# power_electronicsV2_1.net
KiCad netlist of a schematic drawn in EAGLE
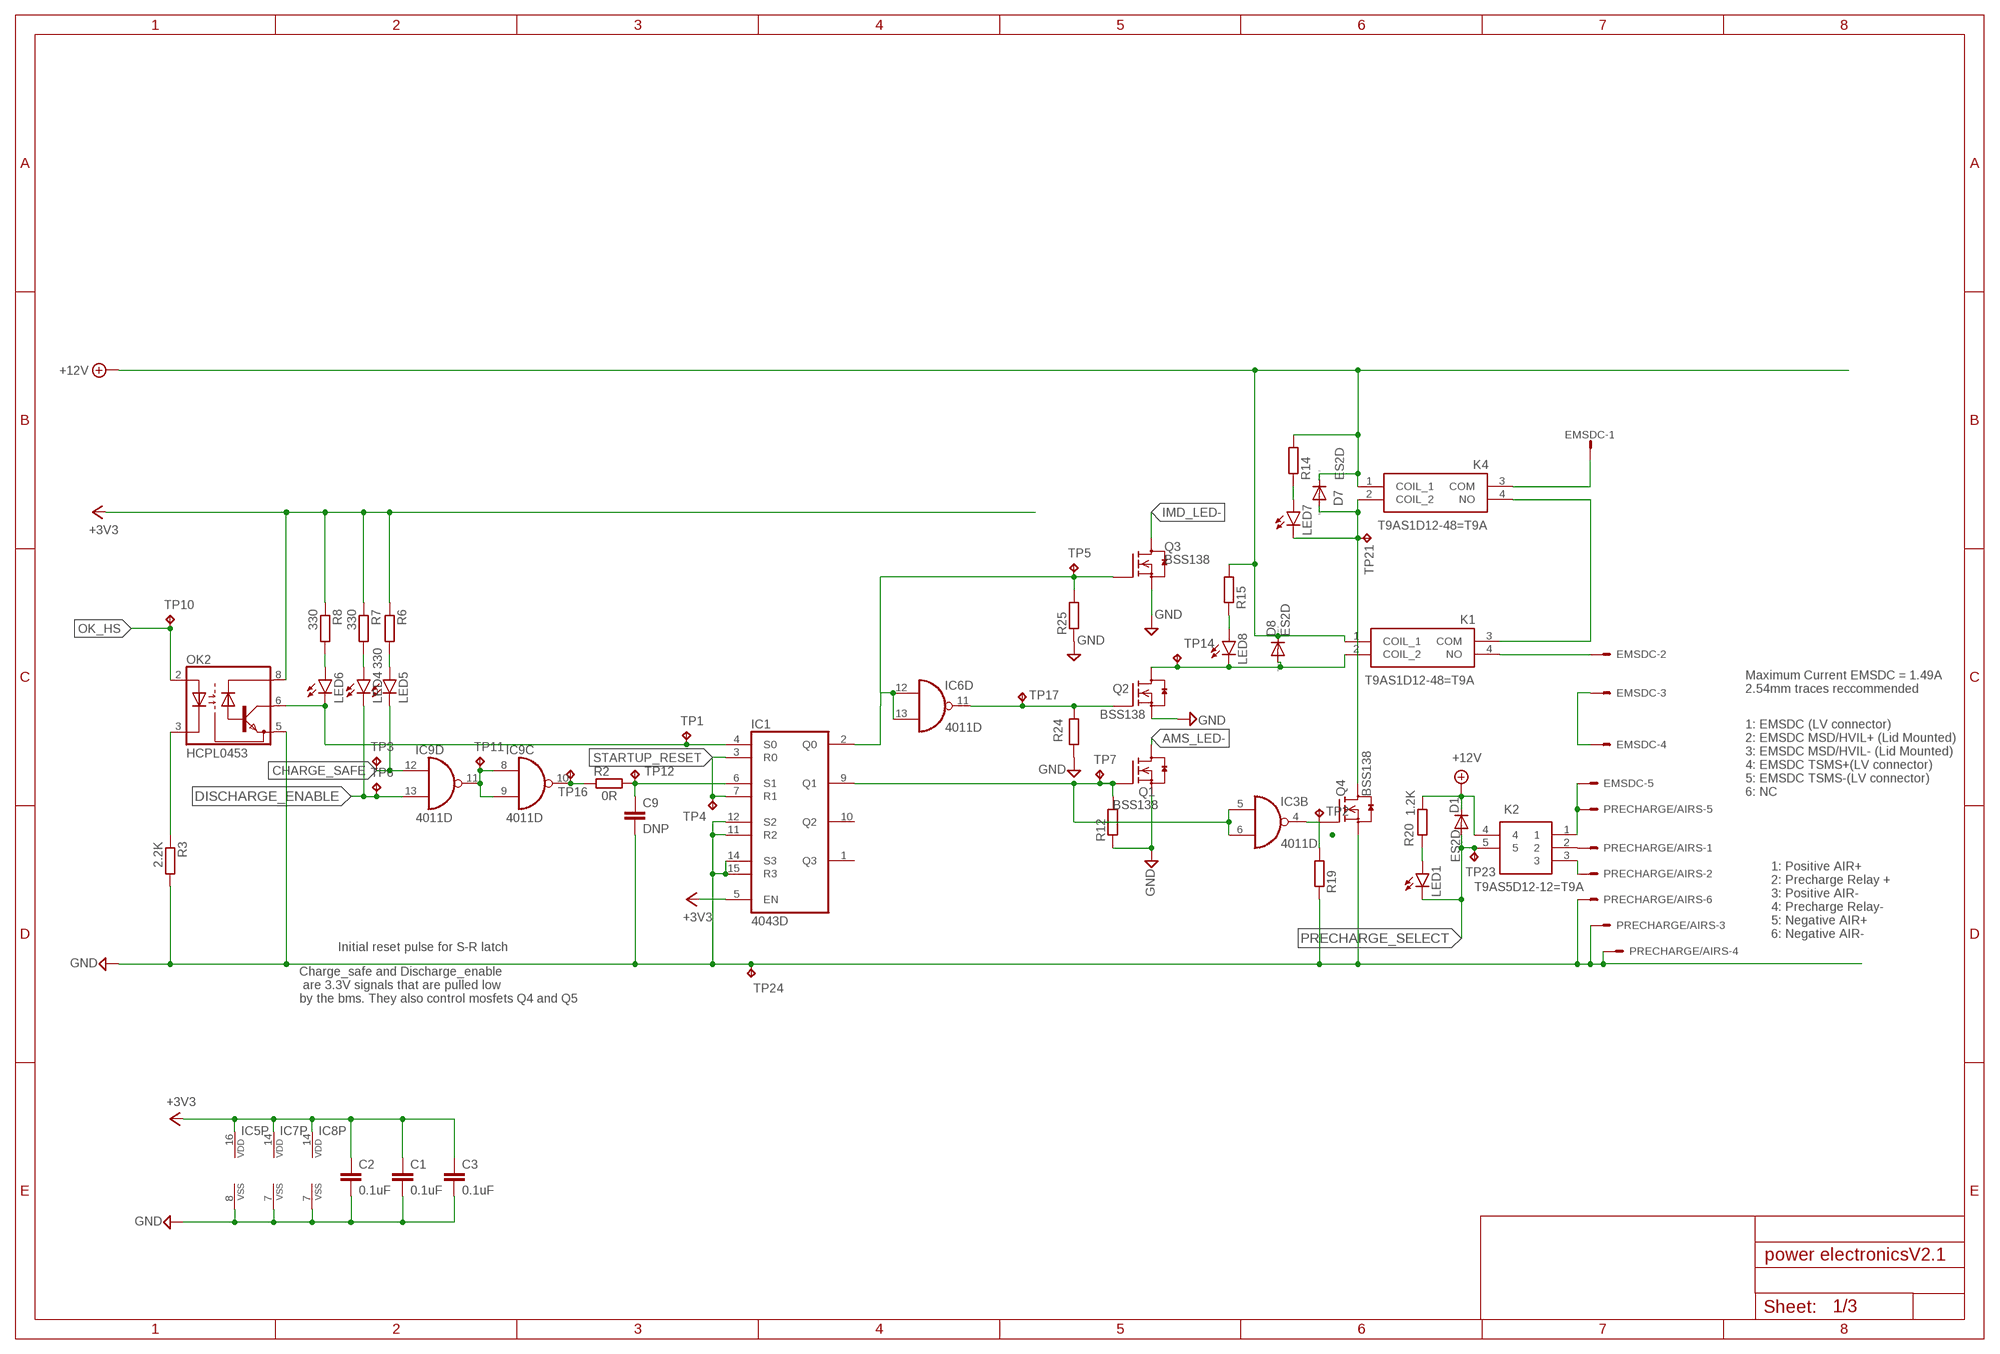
[diagram p0: schematic, sheet 1]
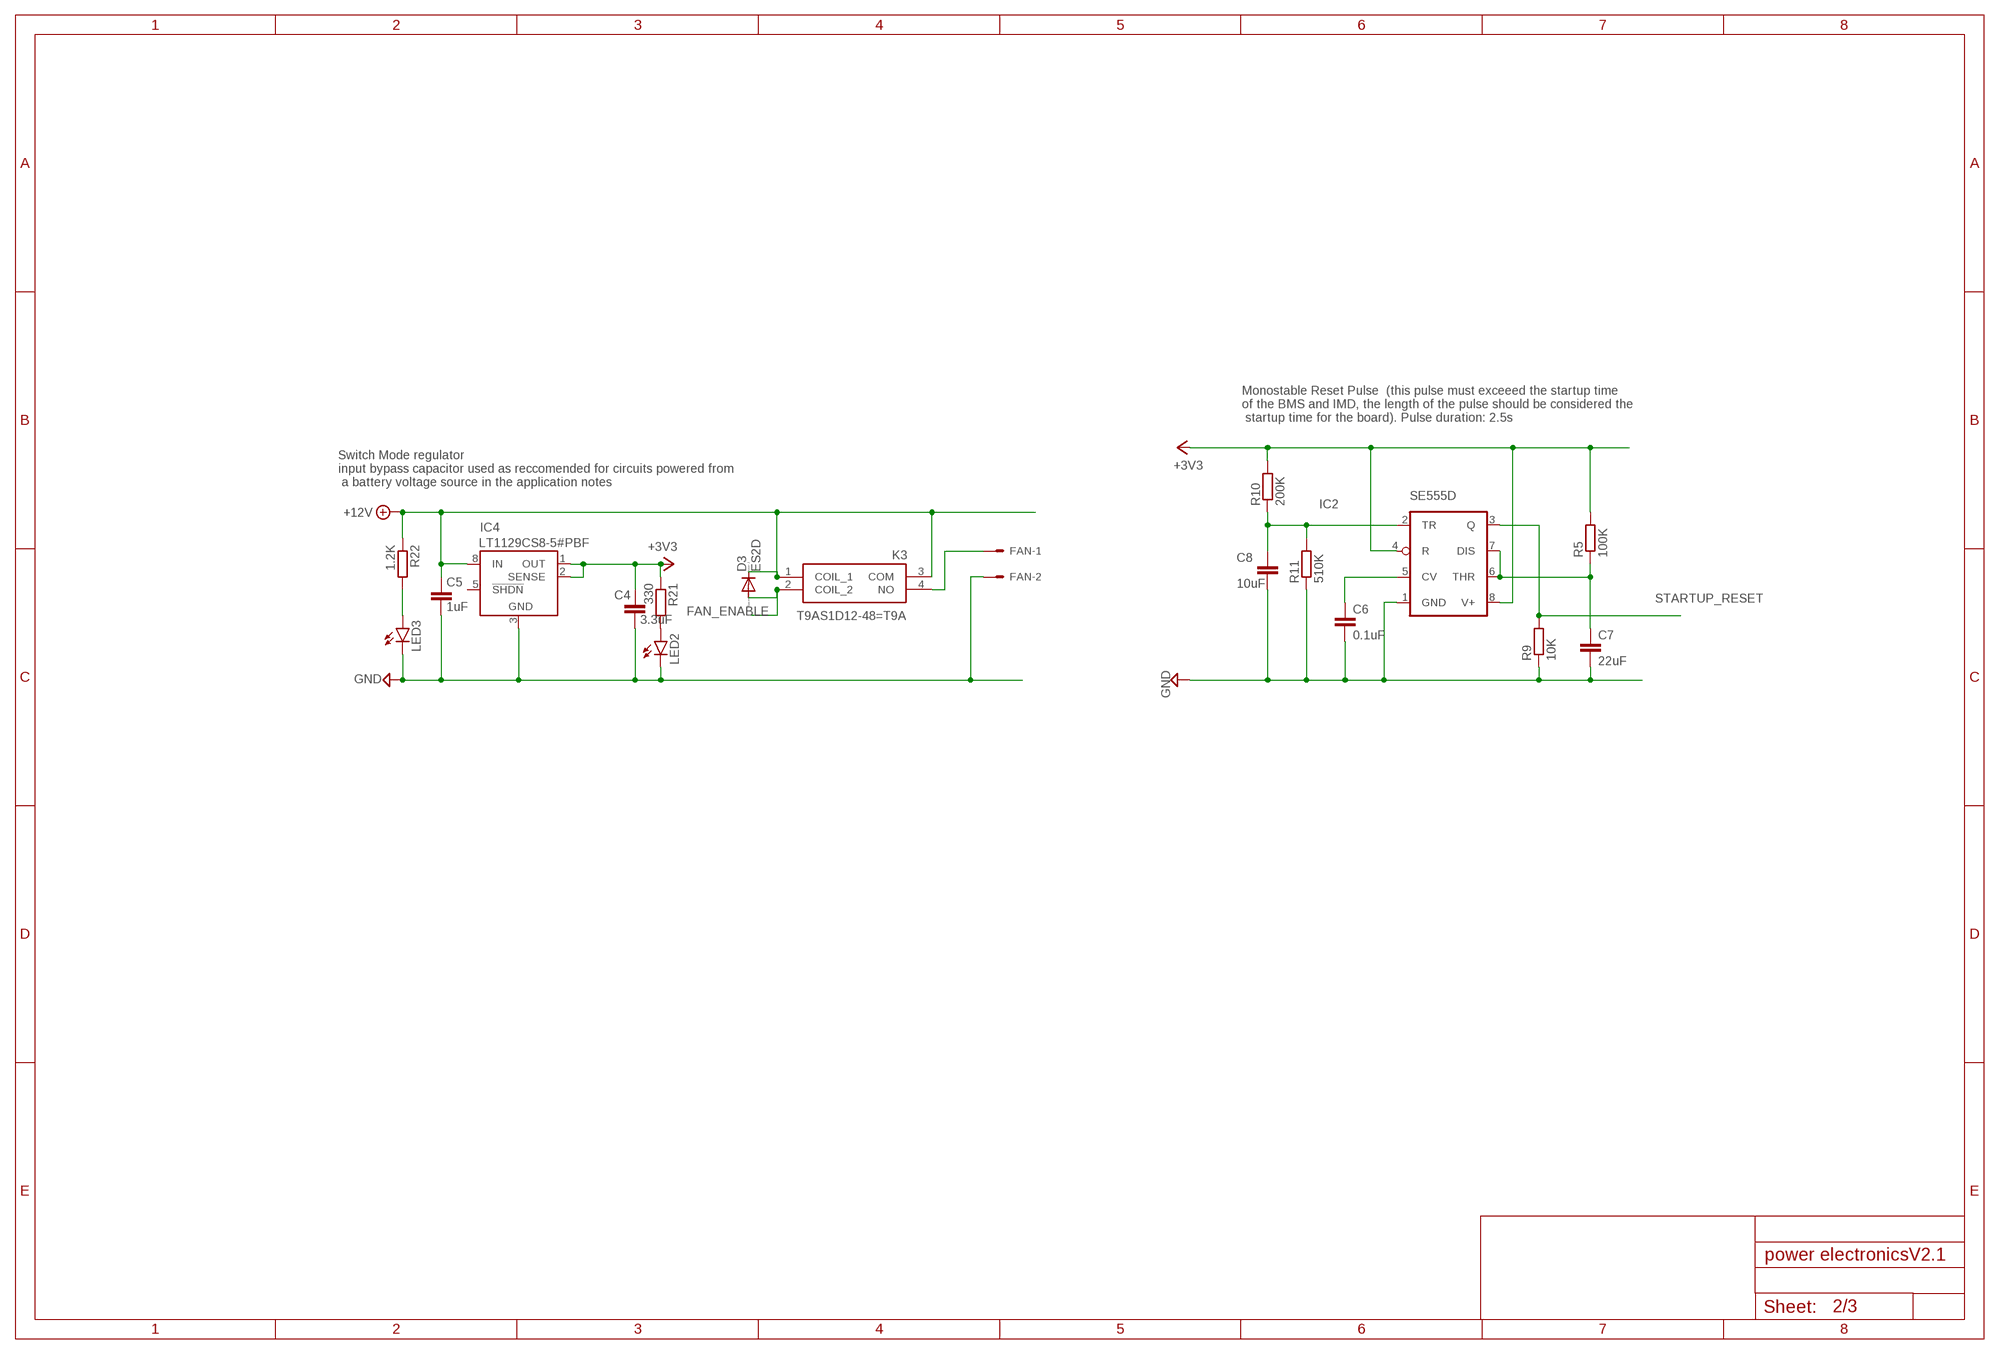
[diagram p1: schematic, sheet 2]
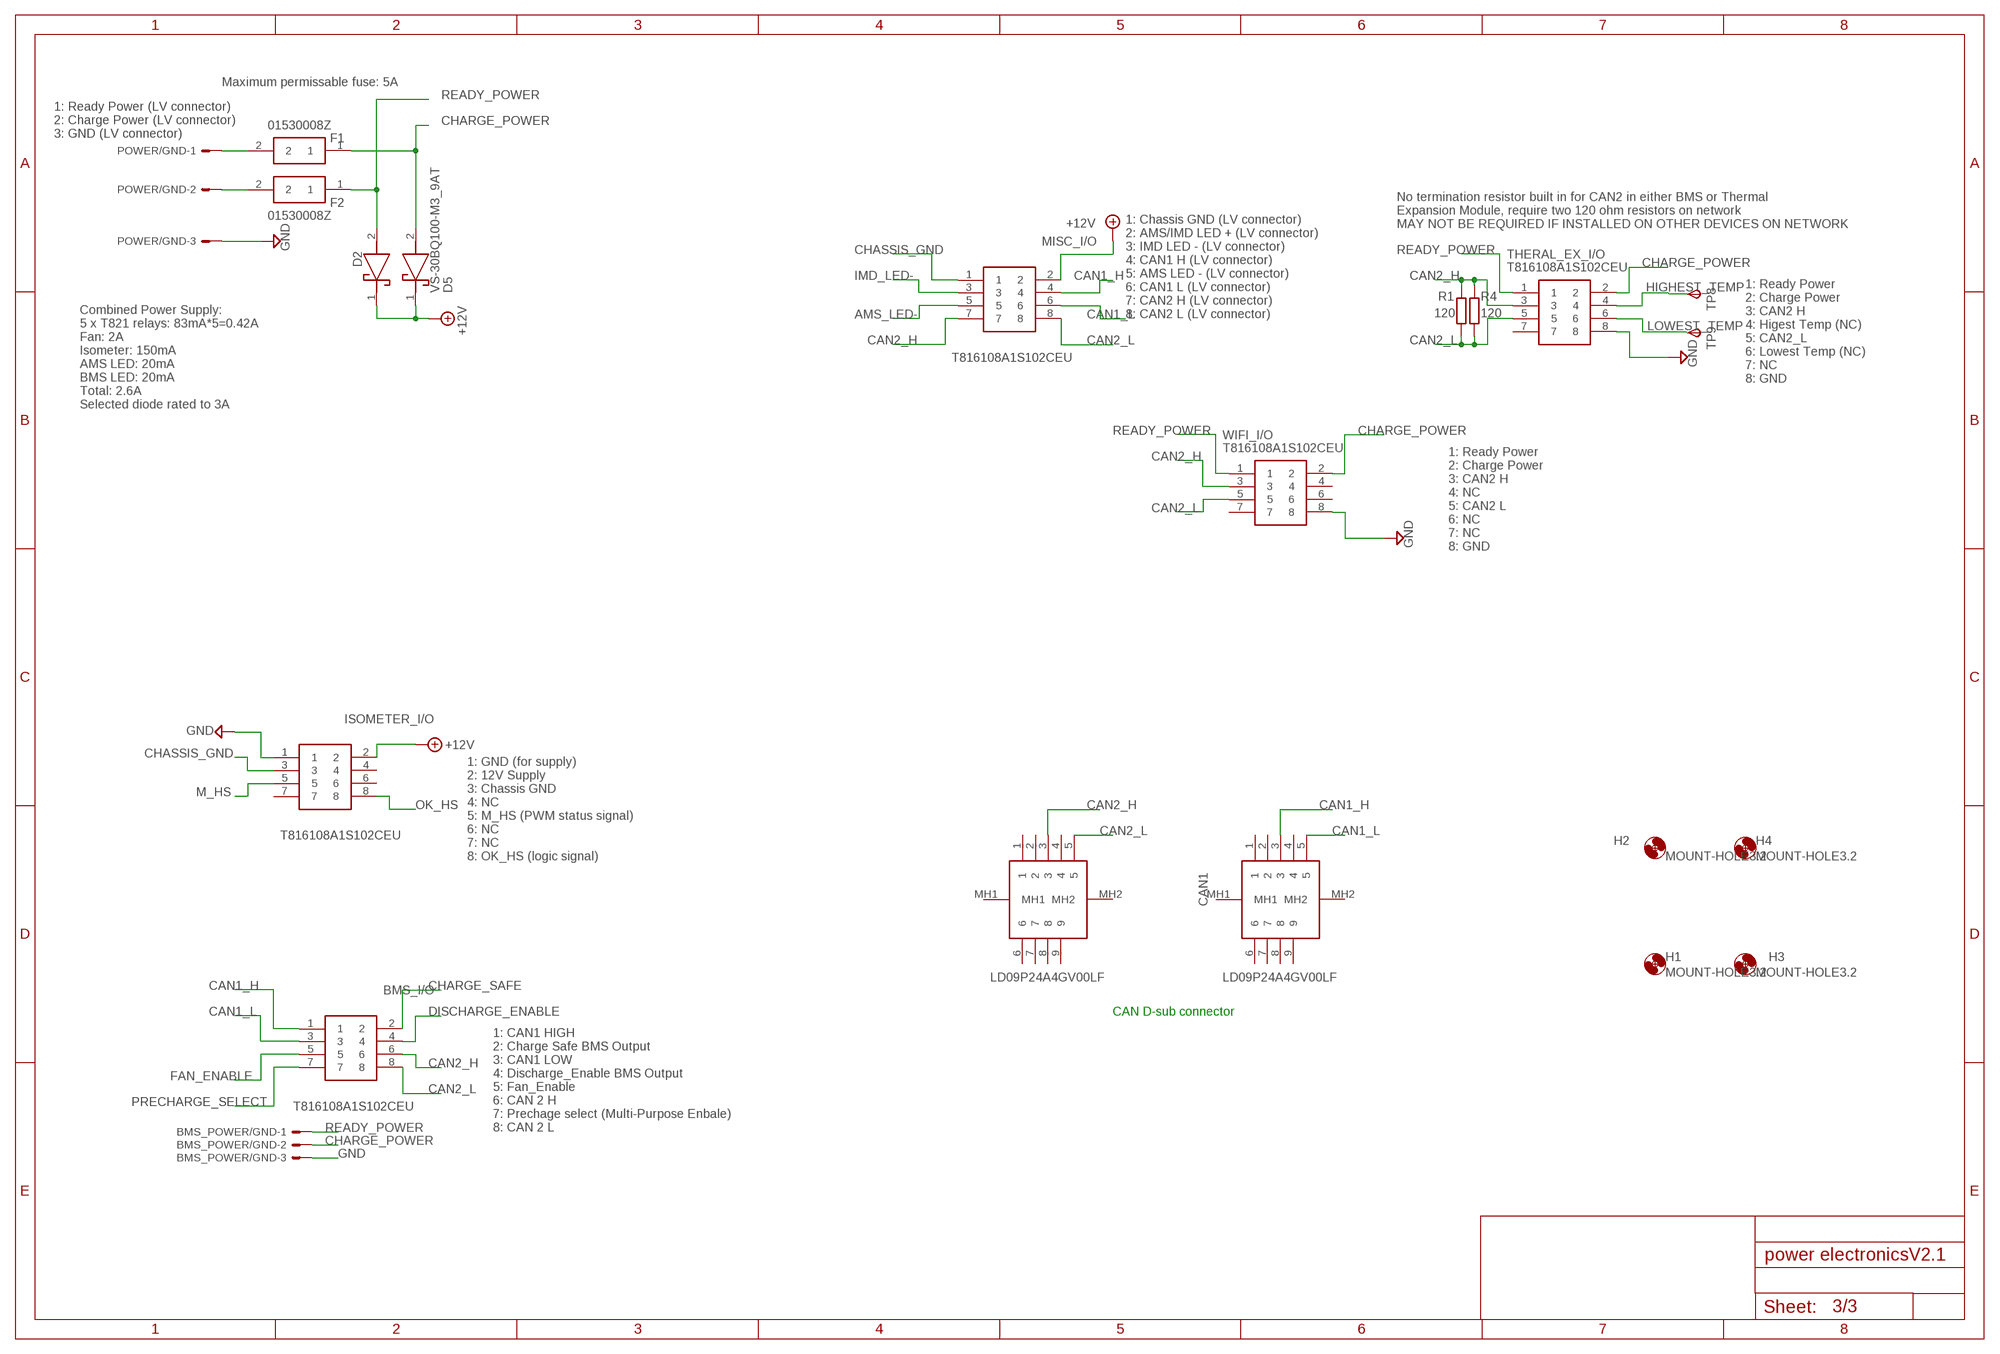
[diagram p2: schematic, sheet 3]

(export (version "E")
  (design (tool "Eeschema 10.0.6"))
  (components
    (comp (ref "C4")
      (value "3.3uF")
      (footprint "eagle-import:C0805")
      (libsource (lib "eagle-import") (part "C-EUC0805"))
    )
    (comp (ref "C5")
      (value "1uF")
      (footprint "eagle-import:C0805")
      (libsource (lib "eagle-import") (part "C-EUC0805"))
    )
    (comp (ref "C6")
      (value "0.1uF")
      (footprint "eagle-import:C0805")
      (libsource (lib "eagle-import") (part "C-EUC0805"))
    )
    (comp (ref "C7")
      (value "22uF")
      (footprint "eagle-import:C1206")
      (libsource (lib "eagle-import") (part "C-EUC1206"))
    )
    (comp (ref "C8")
      (value "10uF")
      (footprint "eagle-import:C0805")
      (libsource (lib "eagle-import") (part "C-EUC0805"))
    )
    (comp (ref "D3")
      (value "ES2D")
      (footprint "eagle-import:SMB")
      (libsource (lib "eagle-import") (part "ES2D"))
    )
    (comp (ref "FAN")
      (value "KK-156-2")
      (footprint "eagle-import:KK-156-2")
      (fields (field (name "MF") "MOLEX"))
      (libsource (lib "eagle-import") (part "KK-156-2"))
    )
    (comp (ref "IC2")
      (value "SE555D")
      (footprint "eagle-import:SO08")
      (libsource (lib "eagle-import") (part "555DSE"))
    )
    (comp (ref "IC4")
      (value "LT1129CS8")
      (footprint "eagle-import:SOIC8")
      (fields (field (name "MPN") "LT1129CS8-5#PBF"))
      (libsource (lib "eagle-import") (part "LT1129CS8"))
    )
    (comp (ref "K3")
      (value "T9AS1D12-48=T9A")
      (footprint "eagle-import:T9AS1D1248T9A")
      (fields (field (name "RS_PART_NUMBER") "6802534P"))
      (libsource (lib "eagle-import") (part "T9AS1D12-48=T9A"))
    )
    (comp (ref "LED2")
      (value "LEDSML0805")
      (footprint "eagle-import:SML0805")
      (libsource (lib "eagle-import") (part "LEDSML0805"))
    )
    (comp (ref "LED3")
      (value "LEDSML0805")
      (footprint "eagle-import:SML0805")
      (libsource (lib "eagle-import") (part "LEDSML0805"))
    )
    (comp (ref "R5")
      (value "100K")
      (footprint "eagle-import:R0805")
      (libsource (lib "eagle-import") (part "R-EU_R0805"))
    )
    (comp (ref "R9")
      (value "10K")
      (footprint "eagle-import:R0805")
      (libsource (lib "eagle-import") (part "R-EU_R0805"))
    )
    (comp (ref "R10")
      (value "200K")
      (footprint "eagle-import:R0805")
      (libsource (lib "eagle-import") (part "R-EU_R0805"))
    )
    (comp (ref "R11")
      (value "510K")
      (footprint "eagle-import:R0805")
      (libsource (lib "eagle-import") (part "R-EU_R0805"))
    )
    (comp (ref "R21")
      (value "330")
      (footprint "eagle-import:R0805")
      (libsource (lib "eagle-import") (part "R-EU_R0805"))
    )
    (comp (ref "R22")
      (value "1.2K")
      (footprint "eagle-import:R0805")
      (libsource (lib "eagle-import") (part "R-EU_R0805"))
    )
    (comp (ref "BMS_I/O")
      (value "T816108A1S102CEU")
      (footprint "eagle-import:T816108A1S102CEU")
      (libsource (lib "eagle-import") (part "T816108A1S102CEU"))
    )
    (comp (ref "BMS_POWER/GND")
      (value "KK-156-3")
      (footprint "eagle-import:KK-156-3")
      (fields (field (name "MF") "MOLEX"))
      (libsource (lib "eagle-import") (part "KK-156-3"))
    )
    (comp (ref "CAN1")
      (value "LD09P24A4GV00LF")
      (footprint "eagle-import:LD09P24A4GV00LF")
      (fields (field (name "MOUSER_PART_NUMBER") "649-LD09P24A4GV00LF"))
      (libsource (lib "eagle-import") (part "LD09P24A4GV00LF"))
    )
    (comp (ref "CAN2")
      (value "LD09P24A4GV00LF")
      (footprint "eagle-import:LD09P24A4GV00LF")
      (fields (field (name "MOUSER_PART_NUMBER") "649-LD09P24A4GV00LF"))
      (libsource (lib "eagle-import") (part "LD09P24A4GV00LF"))
    )
    (comp (ref "D2")
      (value "VS-30BQ100-M3_9AT")
      (footprint "eagle-import:DIOM7959X262N")
      (fields
        (field (name "MANUFACTURER_PART_NUMBER") "VS-30BQ100-M3/9AT")
        (field (name "MOUSER_PART_NUMBER") "78-VS-30BQ100-M39AT")
      )
      (libsource (lib "eagle-import") (part "VS-30BQ100-M3_9AT"))
    )
    (comp (ref "D5")
      (value "VS-30BQ100-M3_9AT")
      (footprint "eagle-import:DIOM7959X262N")
      (fields
        (field (name "MANUFACTURER_PART_NUMBER") "VS-30BQ100-M3/9AT")
        (field (name "MOUSER_PART_NUMBER") "78-VS-30BQ100-M39AT")
      )
      (libsource (lib "eagle-import") (part "VS-30BQ100-M3_9AT"))
    )
    (comp (ref "F1")
      (value "01530008Z")
      (footprint "eagle-import:01530008")
      (fields (field (name "RS_PART_NUMBER") "3607317"))
      (libsource (lib "eagle-import") (part "01530008Z"))
    )
    (comp (ref "F2")
      (value "01530008Z")
      (footprint "eagle-import:01530008")
      (fields (field (name "RS_PART_NUMBER") "3607317"))
      (libsource (lib "eagle-import") (part "01530008Z"))
    )
    (comp (ref "H1")
      (value "MOUNT-HOLE3.2")
      (footprint "eagle-import:3,2")
      (libsource (lib "eagle-import") (part "MOUNT-HOLE3.2"))
    )
    (comp (ref "H2")
      (value "MOUNT-HOLE3.2")
      (footprint "eagle-import:3,2")
      (libsource (lib "eagle-import") (part "MOUNT-HOLE3.2"))
    )
    (comp (ref "H3")
      (value "MOUNT-HOLE3.2")
      (footprint "eagle-import:3,2")
      (libsource (lib "eagle-import") (part "MOUNT-HOLE3.2"))
    )
    (comp (ref "H4")
      (value "MOUNT-HOLE3.2")
      (footprint "eagle-import:3,2")
      (libsource (lib "eagle-import") (part "MOUNT-HOLE3.2"))
    )
    (comp (ref "ISOMETER_I/O")
      (value "T816108A1S102CEU")
      (footprint "eagle-import:T816108A1S102CEU")
      (libsource (lib "eagle-import") (part "T816108A1S102CEU"))
    )
    (comp (ref "MISC_I/O")
      (value "T816108A1S102CEU")
      (footprint "eagle-import:T816108A1S102CEU")
      (libsource (lib "eagle-import") (part "T816108A1S102CEU"))
    )
    (comp (ref "POWER/GND")
      (value "KK-156-3")
      (footprint "eagle-import:KK-156-3")
      (fields (field (name "MF") "MOLEX"))
      (libsource (lib "eagle-import") (part "KK-156-3"))
    )
    (comp (ref "R1")
      (value "120")
      (footprint "eagle-import:R1206")
      (libsource (lib "eagle-import") (part "R-EU_R1206"))
    )
    (comp (ref "R4")
      (value "120")
      (footprint "eagle-import:R1206")
      (libsource (lib "eagle-import") (part "R-EU_R1206"))
    )
    (comp (ref "THERAL_EX_I/O")
      (value "T816108A1S102CEU")
      (footprint "eagle-import:T816108A1S102CEU")
      (libsource (lib "eagle-import") (part "T816108A1S102CEU"))
    )
    (comp (ref "TP8")
      (value "TPSTP11R")
      (footprint "eagle-import:TP11R")
      (libsource (lib "eagle-import") (part "TPSTP11R"))
    )
    (comp (ref "TP9")
      (value "TPSTP11R")
      (footprint "eagle-import:TP11R")
      (libsource (lib "eagle-import") (part "TPSTP11R"))
    )
    (comp (ref "WIFI_I/O")
      (value "T816108A1S102CEU")
      (footprint "eagle-import:T816108A1S102CEU")
      (libsource (lib "eagle-import") (part "T816108A1S102CEU"))
    )
    (comp (ref "C1")
      (value "0.1uF")
      (footprint "eagle-import:C0805")
      (libsource (lib "eagle-import") (part "C-EUC0805"))
    )
    (comp (ref "C2")
      (value "0.1uF")
      (footprint "eagle-import:C0805")
      (libsource (lib "eagle-import") (part "C-EUC0805"))
    )
    (comp (ref "C3")
      (value "0.1uF")
      (footprint "eagle-import:C0805")
      (libsource (lib "eagle-import") (part "C-EUC0805"))
    )
    (comp (ref "C9")
      (value "DNP")
      (footprint "eagle-import:C0805K")
      (libsource (lib "eagle-import") (part "C-EUC0805K"))
    )
    (comp (ref "D1")
      (value "ES2D")
      (footprint "eagle-import:SMB")
      (libsource (lib "eagle-import") (part "ES2D"))
    )
    (comp (ref "D7")
      (value "ES2D")
      (footprint "eagle-import:SMB")
      (libsource (lib "eagle-import") (part "ES2D"))
    )
    (comp (ref "D8")
      (value "ES2D")
      (footprint "eagle-import:SMB")
      (libsource (lib "eagle-import") (part "ES2D"))
    )
    (comp (ref "EMSDC")
      (value "KK-156-6")
      (footprint "eagle-import:KK-156-6")
      (fields (field (name "MF") "MOLEX"))
      (libsource (lib "eagle-import") (part "KK-156-6"))
    )
    (comp (ref "IC1")
      (value "4043D")
      (footprint "eagle-import:SO16")
      (libsource (lib "eagle-import") (part "4043D"))
    )
    (comp (ref "IC3")
      (value "4011D")
      (footprint "eagle-import:SO14")
      (libsource (lib "eagle-import") (part "4011D"))
    )
    (comp (ref "IC5")
      (value "4043D")
      (footprint "eagle-import:SO16")
      (libsource (lib "eagle-import") (part "4043D"))
    )
    (comp (ref "IC6")
      (value "4011D")
      (footprint "eagle-import:SO14")
      (libsource (lib "eagle-import") (part "4011D"))
    )
    (comp (ref "IC7")
      (value "4011D")
      (footprint "eagle-import:SO14")
      (libsource (lib "eagle-import") (part "4011D"))
    )
    (comp (ref "IC8")
      (value "4011D")
      (footprint "eagle-import:SO14")
      (libsource (lib "eagle-import") (part "4011D"))
    )
    (comp (ref "IC9")
      (value "4011D")
      (footprint "eagle-import:SO14")
      (libsource (lib "eagle-import") (part "4011D"))
    )
    (comp (ref "K1")
      (value "T9AS1D12-48=T9A")
      (footprint "eagle-import:T9AS1D1248T9A")
      (fields (field (name "RS_PART_NUMBER") "6802534P"))
      (libsource (lib "eagle-import") (part "T9AS1D12-48=T9A"))
    )
    (comp (ref "K2")
      (value "T9AS5D12-12=T9A")
      (footprint "eagle-import:T9AS1D12")
      (fields (field (name "RS_PART_NUMBER") "6802528"))
      (libsource (lib "eagle-import") (part "T9AS5D12-12=T9A"))
    )
    (comp (ref "K4")
      (value "T9AS1D12-48=T9A")
      (footprint "eagle-import:T9AS1D1248T9A")
      (fields (field (name "RS_PART_NUMBER") "6802534P"))
      (libsource (lib "eagle-import") (part "T9AS1D12-48=T9A"))
    )
    (comp (ref "LED1")
      (value "LEDSML0805")
      (footprint "eagle-import:SML0805")
      (libsource (lib "eagle-import") (part "LEDSML0805"))
    )
    (comp (ref "LED4")
      (value "LEDSML0805")
      (footprint "eagle-import:SML0805")
      (libsource (lib "eagle-import") (part "LEDSML0805"))
    )
    (comp (ref "LED5")
      (value "LEDSML0805")
      (footprint "eagle-import:SML0805")
      (libsource (lib "eagle-import") (part "LEDSML0805"))
    )
    (comp (ref "LED6")
      (value "LEDSML0805")
      (footprint "eagle-import:SML0805")
      (libsource (lib "eagle-import") (part "LEDSML0805"))
    )
    (comp (ref "LED7")
      (value "LEDSML0805")
      (footprint "eagle-import:SML0805")
      (libsource (lib "eagle-import") (part "LEDSML0805"))
    )
    (comp (ref "LED8")
      (value "LEDSML0805")
      (footprint "eagle-import:SML0805")
      (libsource (lib "eagle-import") (part "LEDSML0805"))
    )
    (comp (ref "OK2")
      (value "HCPL0453")
      (footprint "eagle-import:SOIC08")
      (fields (field (name "MF") "AGILENT TECHNOLOGIES") (field (name "MPN") "HCPL-0453-000E"))
      (libsource (lib "eagle-import") (part "HCPL0453"))
    )
    (comp (ref "PRECHARGE/AIRS")
      (value "KK-156-6")
      (footprint "eagle-import:KK-156-6")
      (fields (field (name "MF") "MOLEX"))
      (libsource (lib "eagle-import") (part "KK-156-6"))
    )
    (comp (ref "Q1")
      (value "BSS138")
      (footprint "eagle-import:SOT23")
      (libsource (lib "eagle-import") (part "BSS138"))
    )
    (comp (ref "Q2")
      (value "BSS138")
      (footprint "eagle-import:SOT23")
      (libsource (lib "eagle-import") (part "BSS138"))
    )
    (comp (ref "Q3")
      (value "BSS138")
      (footprint "eagle-import:SOT23")
      (libsource (lib "eagle-import") (part "BSS138"))
    )
    (comp (ref "Q4")
      (value "BSS138")
      (footprint "eagle-import:SOT23")
      (libsource (lib "eagle-import") (part "BSS138"))
    )
    (comp (ref "R2")
      (value "0R")
      (footprint "eagle-import:R0805")
      (libsource (lib "eagle-import") (part "R-EU_R0805"))
    )
    (comp (ref "R3")
      (value "2.2K")
      (footprint "eagle-import:R0805")
      (libsource (lib "eagle-import") (part "R-EU_R0805"))
    )
    (comp (ref "R6")
      (value "330")
      (footprint "eagle-import:R0805")
      (libsource (lib "eagle-import") (part "R-EU_R0805"))
    )
    (comp (ref "R7")
      (value "330")
      (footprint "eagle-import:R0805")
      (libsource (lib "eagle-import") (part "R-EU_R0805"))
    )
    (comp (ref "R8")
      (value "330")
      (footprint "eagle-import:R0805")
      (libsource (lib "eagle-import") (part "R-EU_R0805"))
    )
    (comp (ref "R12")
      (value "R-EU_R0805")
      (footprint "eagle-import:R0805")
      (libsource (lib "eagle-import") (part "R-EU_R0805"))
    )
    (comp (ref "R14")
      (value "R-EU_R0805")
      (footprint "eagle-import:R0805")
      (libsource (lib "eagle-import") (part "R-EU_R0805"))
    )
    (comp (ref "R15")
      (value "R-EU_R0805")
      (footprint "eagle-import:R0805")
      (libsource (lib "eagle-import") (part "R-EU_R0805"))
    )
    (comp (ref "R19")
      (value "R-EU_R0805")
      (footprint "eagle-import:R0805")
      (libsource (lib "eagle-import") (part "R-EU_R0805"))
    )
    (comp (ref "R20")
      (value "1.2K")
      (footprint "eagle-import:R0805")
      (libsource (lib "eagle-import") (part "R-EU_R0805"))
    )
    (comp (ref "R24")
      (value "R-EU_R0805")
      (footprint "eagle-import:R0805")
      (libsource (lib "eagle-import") (part "R-EU_R0805"))
    )
    (comp (ref "R25")
      (value "R-EU_R0805")
      (footprint "eagle-import:R0805")
      (libsource (lib "eagle-import") (part "R-EU_R0805"))
    )
    (comp (ref "TP1")
      (value "TPPAD1-17")
      (footprint "eagle-import:P1-17")
      (libsource (lib "eagle-import") (part "TPPAD1-17"))
    )
    (comp (ref "TP2")
      (value "TPPAD1-17")
      (footprint "eagle-import:P1-17")
      (libsource (lib "eagle-import") (part "TPPAD1-17"))
    )
    (comp (ref "TP3")
      (value "TPPAD1-17")
      (footprint "eagle-import:P1-17")
      (libsource (lib "eagle-import") (part "TPPAD1-17"))
    )
    (comp (ref "TP4")
      (value "TPPAD1-17")
      (footprint "eagle-import:P1-17")
      (libsource (lib "eagle-import") (part "TPPAD1-17"))
    )
    (comp (ref "TP5")
      (value "TPPAD1-17")
      (footprint "eagle-import:P1-17")
      (libsource (lib "eagle-import") (part "TPPAD1-17"))
    )
    (comp (ref "TP6")
      (value "TPPAD1-17")
      (footprint "eagle-import:P1-17")
      (libsource (lib "eagle-import") (part "TPPAD1-17"))
    )
    (comp (ref "TP7")
      (value "TPPAD1-17")
      (footprint "eagle-import:P1-17")
      (libsource (lib "eagle-import") (part "TPPAD1-17"))
    )
    (comp (ref "TP10")
      (value "TPPAD1-17")
      (footprint "eagle-import:P1-17")
      (libsource (lib "eagle-import") (part "TPPAD1-17"))
    )
    (comp (ref "TP11")
      (value "TPPAD1-17")
      (footprint "eagle-import:P1-17")
      (libsource (lib "eagle-import") (part "TPPAD1-17"))
    )
    (comp (ref "TP12")
      (value "TPPAD1-17")
      (footprint "eagle-import:P1-17")
      (libsource (lib "eagle-import") (part "TPPAD1-17"))
    )
    (comp (ref "TP14")
      (value "TPPAD1-17")
      (footprint "eagle-import:P1-17")
      (libsource (lib "eagle-import") (part "TPPAD1-17"))
    )
    (comp (ref "TP16")
      (value "TPPAD1-17")
      (footprint "eagle-import:P1-17")
      (libsource (lib "eagle-import") (part "TPPAD1-17"))
    )
    (comp (ref "TP17")
      (value "TPPAD1-17")
      (footprint "eagle-import:P1-17")
      (libsource (lib "eagle-import") (part "TPPAD1-17"))
    )
    (comp (ref "TP21")
      (value "TPPAD1-17")
      (footprint "eagle-import:P1-17")
      (libsource (lib "eagle-import") (part "TPPAD1-17"))
    )
    (comp (ref "TP23")
      (value "TPPAD1-17")
      (footprint "eagle-import:P1-17")
      (libsource (lib "eagle-import") (part "TPPAD1-17"))
    )
    (comp (ref "TP24")
      (value "TPPAD1-17")
      (footprint "eagle-import:P1-17")
      (libsource (lib "eagle-import") (part "TPPAD1-17"))
    )
  )
  (nets
    (net (code "1") (name "+3V3") (class "Default")
      (node (ref "C1") (pin "1") (pinfunction "1_1") (pintype "passive"))
      (node (ref "C2") (pin "1") (pinfunction "1_1") (pintype "passive"))
      (node (ref "C3") (pin "1") (pinfunction "1_1") (pintype "passive"))
      (node (ref "C4") (pin "1") (pinfunction "1_1") (pintype "passive"))
      (node (ref "IC1") (pin "5") (pinfunction "EN_5") (pintype "input"))
      (node (ref "IC2") (pin "4") (pinfunction "R_4") (pintype "input"))
      (node (ref "IC2") (pin "8") (pinfunction "V+_8") (pintype "power_in"))
      (node (ref "IC4") (pin "1") (pinfunction "OUT_1") (pintype "output"))
      (node (ref "IC4") (pin "2") (pinfunction "SENSE_2") (pintype "input"))
      (node (ref "IC5") (pin "16") (pinfunction "VDD_16") (pintype "power_in"))
      (node (ref "IC7") (pin "14") (pinfunction "VDD_14") (pintype "power_in"))
      (node (ref "IC8") (pin "14") (pinfunction "VDD_14") (pintype "power_in"))
      (node (ref "OK2") (pin "8") (pinfunction "VCC_8") (pintype "passive"))
      (node (ref "R10") (pin "2") (pinfunction "2_2") (pintype "passive"))
      (node (ref "R21") (pin "1") (pinfunction "1_1") (pintype "passive"))
      (node (ref "R5") (pin "2") (pinfunction "2_2") (pintype "passive"))
      (node (ref "R6") (pin "1") (pinfunction "1_1") (pintype "passive"))
      (node (ref "R7") (pin "1") (pinfunction "1_1") (pintype "passive"))
      (node (ref "R8") (pin "1") (pinfunction "1_1") (pintype "passive"))
    )
    (net (code "2") (name "+12V") (class "Default")
      (node (ref "C5") (pin "1") (pinfunction "1_1") (pintype "passive"))
      (node (ref "D1") (pin "C") (pinfunction "C_C") (pintype "passive"))
      (node (ref "D2") (pin "1") (pinfunction "K_1") (pintype "bidirectional"))
      (node (ref "D3") (pin "C") (pinfunction "C_C") (pintype "passive"))
      (node (ref "D5") (pin "1") (pinfunction "K_1") (pintype "bidirectional"))
      (node (ref "D7") (pin "C") (pinfunction "C_C") (pintype "passive"))
      (node (ref "D8") (pin "C") (pinfunction "C_C") (pintype "passive"))
      (node (ref "IC4") (pin "8") (pinfunction "IN_8") (pintype "input"))
      (node (ref "ISOMETER_I/O") (pin "2") (pinfunction "2_2") (pintype "bidirectional"))
      (node (ref "K1") (pin "1") (pinfunction "COIL_1_1") (pintype "bidirectional"))
      (node (ref "K2") (pin "4") (pinfunction "4_4") (pintype "bidirectional"))
      (node (ref "K3") (pin "1") (pinfunction "COIL_1_1") (pintype "bidirectional"))
      (node (ref "K3") (pin "3") (pinfunction "COM_3") (pintype "bidirectional"))
      (node (ref "K4") (pin "1") (pinfunction "COIL_1_1") (pintype "bidirectional"))
      (node (ref "MISC_I/O") (pin "2") (pinfunction "2_2") (pintype "bidirectional"))
      (node (ref "R14") (pin "2") (pinfunction "2_2") (pintype "passive"))
      (node (ref "R15") (pin "2") (pinfunction "2_2") (pintype "passive"))
      (node (ref "R20") (pin "1") (pinfunction "1_1") (pintype "passive"))
      (node (ref "R22") (pin "1") (pinfunction "1_1") (pintype "passive"))
    )
    (net (code "3") (name "AMS_LED-") (class "Default")
      (node (ref "MISC_I/O") (pin "5") (pinfunction "5_5") (pintype "bidirectional"))
      (node (ref "Q1") (pin "3") (pinfunction "D_3") (pintype "passive"))
    )
    (net (code "4") (name "CAN1_H") (class "Default")
      (node (ref "BMS_I/O") (pin "1") (pinfunction "1_1") (pintype "bidirectional"))
      (node (ref "CAN1") (pin "3") (pinfunction "3_3") (pintype "bidirectional"))
      (node (ref "MISC_I/O") (pin "4") (pinfunction "4_4") (pintype "bidirectional"))
    )
    (net (code "5") (name "CAN1_L") (class "Default")
      (node (ref "BMS_I/O") (pin "3") (pinfunction "3_3") (pintype "bidirectional"))
      (node (ref "CAN1") (pin "5") (pinfunction "5_5") (pintype "bidirectional"))
      (node (ref "MISC_I/O") (pin "6") (pinfunction "6_6") (pintype "bidirectional"))
    )
    (net (code "6") (name "CAN2_H") (class "Default")
      (node (ref "BMS_I/O") (pin "6") (pinfunction "6_6") (pintype "bidirectional"))
      (node (ref "CAN2") (pin "3") (pinfunction "3_3") (pintype "bidirectional"))
      (node (ref "MISC_I/O") (pin "7") (pinfunction "7_7") (pintype "bidirectional"))
      (node (ref "R1") (pin "1") (pinfunction "1_1") (pintype "passive"))
      (node (ref "R4") (pin "1") (pinfunction "1_1") (pintype "passive"))
      (node (ref "THERAL_EX_I/O") (pin "3") (pinfunction "3_3") (pintype "bidirectional"))
      (node (ref "WIFI_I/O") (pin "3") (pinfunction "3_3") (pintype "bidirectional"))
    )
    (net (code "7") (name "CAN2_L") (class "Default")
      (node (ref "BMS_I/O") (pin "8") (pinfunction "8_8") (pintype "bidirectional"))
      (node (ref "CAN2") (pin "5") (pinfunction "5_5") (pintype "bidirectional"))
      (node (ref "MISC_I/O") (pin "8") (pinfunction "8_8") (pintype "bidirectional"))
      (node (ref "R1") (pin "2") (pinfunction "2_2") (pintype "passive"))
      (node (ref "R4") (pin "2") (pinfunction "2_2") (pintype "passive"))
      (node (ref "THERAL_EX_I/O") (pin "5") (pinfunction "5_5") (pintype "bidirectional"))
      (node (ref "WIFI_I/O") (pin "5") (pinfunction "5_5") (pintype "bidirectional"))
    )
    (net (code "8") (name "CHARGE_POWER") (class "Default")
      (node (ref "BMS_POWER/GND") (pin "2") (pinfunction "S_2") (pintype "passive"))
      (node (ref "D5") (pin "2") (pinfunction "A_2") (pintype "bidirectional"))
      (node (ref "F1") (pin "1") (pinfunction "1_1") (pintype "bidirectional"))
      (node (ref "THERAL_EX_I/O") (pin "2") (pinfunction "2_2") (pintype "bidirectional"))
      (node (ref "WIFI_I/O") (pin "2") (pinfunction "2_2") (pintype "bidirectional"))
    )
    (net (code "9") (name "CHARGE_SAFE") (class "Default")
      (node (ref "BMS_I/O") (pin "2") (pinfunction "2_2") (pintype "bidirectional"))
      (node (ref "IC9") (pin "12") (pinfunction "I0_12") (pintype "input"))
      (node (ref "LED5") (pin "C") (pinfunction "C_C") (pintype "passive"))
      (node (ref "TP3") (pin "TP") (pinfunction "TP_TP") (pintype "input"))
    )
    (net (code "10") (name "CHASSIS_GND") (class "Default")
      (node (ref "ISOMETER_I/O") (pin "3") (pinfunction "3_3") (pintype "bidirectional"))
      (node (ref "MISC_I/O") (pin "1") (pinfunction "1_1") (pintype "bidirectional"))
    )
    (net (code "11") (name "DISCHARGE_ENABLE") (class "Default")
      (node (ref "BMS_I/O") (pin "4") (pinfunction "4_4") (pintype "bidirectional"))
      (node (ref "IC1") (pin "9") (pinfunction "Q1_9") (pintype "output"))
      (node (ref "IC3") (pin "5") (pinfunction "I0_5") (pintype "input"))
      (node (ref "IC3") (pin "6") (pinfunction "I1_6") (pintype "input"))
      (node (ref "IC9") (pin "13") (pinfunction "I1_13") (pintype "input"))
      (node (ref "LED4") (pin "C") (pinfunction "C_C") (pintype "passive"))
      (node (ref "Q1") (pin "1") (pinfunction "G_1") (pintype "passive"))
      (node (ref "R12") (pin "2") (pinfunction "2_2") (pintype "passive"))
      (node (ref "TP6") (pin "TP") (pinfunction "TP_TP") (pintype "input"))
      (node (ref "TP7") (pin "TP") (pinfunction "TP_TP") (pintype "input"))
    )
    (net (code "12") (name "FAN_ENABLE") (class "Default")
      (node (ref "BMS_I/O") (pin "5") (pinfunction "5_5") (pintype "bidirectional"))
      (node (ref "D3") (pin "A") (pinfunction "A_A") (pintype "passive"))
      (node (ref "K3") (pin "2") (pinfunction "COIL_2_2") (pintype "bidirectional"))
    )
    (net (code "13") (name "GND") (class "Default")
      (node (ref "BMS_POWER/GND") (pin "3") (pinfunction "S_3") (pintype "passive"))
      (node (ref "C1") (pin "2") (pinfunction "2_2") (pintype "passive"))
      (node (ref "C2") (pin "2") (pinfunction "2_2") (pintype "passive"))
      (node (ref "C3") (pin "2") (pinfunction "2_2") (pintype "passive"))
      (node (ref "C4") (pin "2") (pinfunction "2_2") (pintype "passive"))
      (node (ref "C5") (pin "2") (pinfunction "2_2") (pintype "passive"))
      (node (ref "C6") (pin "2") (pinfunction "2_2") (pintype "passive"))
      (node (ref "C7") (pin "2") (pinfunction "2_2") (pintype "passive"))
      (node (ref "C8") (pin "2") (pinfunction "2_2") (pintype "passive"))
      (node (ref "C9") (pin "2") (pinfunction "2_2") (pintype "passive"))
      (node (ref "FAN") (pin "2") (pinfunction "S_2") (pintype "passive"))
      (node (ref "IC1") (pin "11") (pinfunction "R2_11") (pintype "input"))
      (node (ref "IC1") (pin "12") (pinfunction "S2_12") (pintype "input"))
      (node (ref "IC1") (pin "14") (pinfunction "S3_14") (pintype "input"))
      (node (ref "IC1") (pin "15") (pinfunction "R3_15") (pintype "input"))
      (node (ref "IC2") (pin "1") (pinfunction "GND_1") (pintype "power_in"))
      (node (ref "IC4") (pin "3") (pinfunction "GND_3") (pintype "power_in"))
      (node (ref "IC5") (pin "8") (pinfunction "VSS_8") (pintype "power_in"))
      (node (ref "IC7") (pin "7") (pinfunction "VSS_7") (pintype "power_in"))
      (node (ref "IC8") (pin "7") (pinfunction "VSS_7") (pintype "power_in"))
      (node (ref "ISOMETER_I/O") (pin "1") (pinfunction "1_1") (pintype "bidirectional"))
      (node (ref "LED2") (pin "C") (pinfunction "C_C") (pintype "passive"))
      (node (ref "LED3") (pin "C") (pinfunction "C_C") (pintype "passive"))
      (node (ref "OK2") (pin "5") (pinfunction "GND_5") (pintype "passive"))
      (node (ref "POWER/GND") (pin "3") (pinfunction "S_3") (pintype "passive"))
      (node (ref "PRECHARGE/AIRS") (pin "3") (pinfunction "S_3") (pintype "passive"))
      (node (ref "PRECHARGE/AIRS") (pin "4") (pinfunction "S_4") (pintype "passive"))
      (node (ref "PRECHARGE/AIRS") (pin "6") (pinfunction "S_6") (pintype "passive"))
      (node (ref "Q1") (pin "2") (pinfunction "S_2") (pintype "passive"))
      (node (ref "Q2") (pin "2") (pinfunction "S_2") (pintype "passive"))
      (node (ref "Q3") (pin "2") (pinfunction "S_2") (pintype "passive"))
      (node (ref "Q4") (pin "2") (pinfunction "S_2") (pintype "passive"))
      (node (ref "R11") (pin "1") (pinfunction "1_1") (pintype "passive"))
      (node (ref "R12") (pin "1") (pinfunction "1_1") (pintype "passive"))
      (node (ref "R19") (pin "1") (pinfunction "1_1") (pintype "passive"))
      (node (ref "R24") (pin "1") (pinfunction "1_1") (pintype "passive"))
      (node (ref "R25") (pin "1") (pinfunction "1_1") (pintype "passive"))
      (node (ref "R3") (pin "2") (pinfunction "2_2") (pintype "passive"))
      (node (ref "R9") (pin "1") (pinfunction "1_1") (pintype "passive"))
      (node (ref "THERAL_EX_I/O") (pin "8") (pinfunction "8_8") (pintype "bidirectional"))
      (node (ref "TP24") (pin "TP") (pinfunction "TP_TP") (pintype "input"))
      (node (ref "WIFI_I/O") (pin "8") (pinfunction "8_8") (pintype "bidirectional"))
    )
    (net (code "14") (name "HIGHEST_TEMP") (class "Default")
      (node (ref "THERAL_EX_I/O") (pin "4") (pinfunction "4_4") (pintype "bidirectional"))
      (node (ref "TP8") (pin "TP") (pinfunction "PP_TP") (pintype "input"))
    )
    (net (code "15") (name "IMD_LED-") (class "Default")
      (node (ref "MISC_I/O") (pin "3") (pinfunction "3_3") (pintype "bidirectional"))
      (node (ref "Q3") (pin "3") (pinfunction "D_3") (pintype "passive"))
    )
    (net (code "16") (name "LOWEST_TEMP") (class "Default")
      (node (ref "THERAL_EX_I/O") (pin "6") (pinfunction "6_6") (pintype "bidirectional"))
      (node (ref "TP9") (pin "TP") (pinfunction "PP_TP") (pintype "input"))
    )
    (net (code "17") (name "M_HS") (class "Default")
      (node (ref "ISOMETER_I/O") (pin "5") (pinfunction "5_5") (pintype "bidirectional"))
    )
    (net (code "18") (name "Net-(EMSDCA-S)") (class "Default")
      (node (ref "EMSDC") (pin "1") (pinfunction "S_1") (pintype "passive"))
      (node (ref "K4") (pin "3") (pinfunction "COM_3") (pintype "bidirectional"))
    )
    (net (code "19") (name "Net-(EMSDCB-S)") (class "Default")
      (node (ref "EMSDC") (pin "2") (pinfunction "S_2") (pintype "passive"))
      (node (ref "K1") (pin "4") (pinfunction "NO_4") (pintype "bidirectional"))
    )
    (net (code "20") (name "Net-(EMSDCC-S)") (class "Default")
      (node (ref "EMSDC") (pin "3") (pinfunction "S_3") (pintype "passive"))
      (node (ref "EMSDC") (pin "4") (pinfunction "S_4") (pintype "passive"))
    )
    (net (code "21") (name "Net-(EMSDCE-S)") (class "Default")
      (node (ref "EMSDC") (pin "5") (pinfunction "S_5") (pintype "passive"))
      (node (ref "K2") (pin "1") (pinfunction "1_1") (pintype "bidirectional"))
      (node (ref "PRECHARGE/AIRS") (pin "5") (pinfunction "S_5") (pintype "passive"))
    )
    (net (code "22") (name "Net-(FANA-S)") (class "Default")
      (node (ref "FAN") (pin "1") (pinfunction "S_1") (pintype "passive"))
      (node (ref "K3") (pin "4") (pinfunction "NO_4") (pintype "bidirectional"))
    )
    (net (code "23") (name "Net-(IC1A-Q0)") (class "Default")
      (node (ref "IC1") (pin "2") (pinfunction "Q0_2") (pintype "output"))
      (node (ref "IC6") (pin "12") (pinfunction "I0_12") (pintype "input"))
      (node (ref "IC6") (pin "13") (pinfunction "I1_13") (pintype "input"))
      (node (ref "Q3") (pin "1") (pinfunction "G_1") (pintype "passive"))
      (node (ref "R25") (pin "2") (pinfunction "2_2") (pintype "passive"))
      (node (ref "TP5") (pin "TP") (pinfunction "TP_TP") (pintype "input"))
    )
    (net (code "24") (name "Net-(IC1A-S0)") (class "Default")
      (node (ref "IC1") (pin "4") (pinfunction "S0_4") (pintype "input"))
      (node (ref "LED6") (pin "C") (pinfunction "C_C") (pintype "passive"))
      (node (ref "OK2") (pin "6") (pinfunction "VO_6") (pintype "passive"))
      (node (ref "TP1") (pin "TP") (pinfunction "TP_TP") (pintype "input"))
    )
    (net (code "25") (name "Net-(IC1A-S1)") (class "Default")
      (node (ref "C9") (pin "1") (pinfunction "1_1") (pintype "passive"))
      (node (ref "IC1") (pin "6") (pinfunction "S1_6") (pintype "input"))
      (node (ref "R2") (pin "2") (pinfunction "2_2") (pintype "passive"))
      (node (ref "TP12") (pin "TP") (pinfunction "TP_TP") (pintype "input"))
    )
    (net (code "26") (name "Net-(IC2-CV)") (class "Default")
      (node (ref "C6") (pin "1") (pinfunction "1_1") (pintype "passive"))
      (node (ref "IC2") (pin "5") (pinfunction "CV_5") (pintype "input"))
    )
    (net (code "27") (name "Net-(IC2-DIS)") (class "Default")
      (node (ref "C7") (pin "1") (pinfunction "1_1") (pintype "passive"))
      (node (ref "IC2") (pin "6") (pinfunction "THR_6") (pintype "input"))
      (node (ref "IC2") (pin "7") (pinfunction "DIS_7") (pintype "input"))
      (node (ref "R5") (pin "1") (pinfunction "1_1") (pintype "passive"))
    )
    (net (code "28") (name "Net-(IC2-TR)") (class "Default")
      (node (ref "C8") (pin "1") (pinfunction "1_1") (pintype "passive"))
      (node (ref "IC2") (pin "2") (pinfunction "TR_2") (pintype "input"))
      (node (ref "R10") (pin "1") (pinfunction "1_1") (pintype "passive"))
      (node (ref "R11") (pin "2") (pinfunction "2_2") (pintype "passive"))
    )
    (net (code "29") (name "Net-(IC3B-O)") (class "Default")
      (node (ref "IC3") (pin "4") (pinfunction "O_4") (pintype "output"))
      (node (ref "Q4") (pin "1") (pinfunction "G_1") (pintype "passive"))
      (node (ref "R19") (pin "2") (pinfunction "2_2") (pintype "passive"))
      (node (ref "TP2") (pin "TP") (pinfunction "TP_TP") (pintype "input"))
    )
    (net (code "30") (name "Net-(IC6D-O)") (class "Default")
      (node (ref "IC6") (pin "11") (pinfunction "O_11") (pintype "output"))
      (node (ref "Q2") (pin "1") (pinfunction "G_1") (pintype "passive"))
      (node (ref "R24") (pin "2") (pinfunction "2_2") (pintype "passive"))
      (node (ref "TP17") (pin "TP") (pinfunction "TP_TP") (pintype "input"))
    )
    (net (code "31") (name "Net-(IC9C-I0)") (class "Default")
      (node (ref "IC9") (pin "11") (pinfunction "O_11") (pintype "output"))
      (node (ref "IC9") (pin "8") (pinfunction "I0_8") (pintype "input"))
      (node (ref "IC9") (pin "9") (pinfunction "I1_9") (pintype "input"))
      (node (ref "TP11") (pin "TP") (pinfunction "TP_TP") (pintype "input"))
    )
    (net (code "32") (name "Net-(IC9C-O)") (class "Default")
      (node (ref "IC9") (pin "10") (pinfunction "O_10") (pintype "output"))
      (node (ref "R2") (pin "1") (pinfunction "1_1") (pintype "passive"))
      (node (ref "TP16") (pin "TP") (pinfunction "TP_TP") (pintype "input"))
    )
    (net (code "33") (name "Net-(K1-COIL_2)") (class "Default")
      (node (ref "D8") (pin "A") (pinfunction "A_A") (pintype "passive"))
      (node (ref "K1") (pin "2") (pinfunction "COIL_2_2") (pintype "bidirectional"))
      (node (ref "LED8") (pin "C") (pinfunction "C_C") (pintype "passive"))
      (node (ref "Q2") (pin "3") (pinfunction "D_3") (pintype "passive"))
      (node (ref "TP14") (pin "TP") (pinfunction "TP_TP") (pintype "input"))
    )
    (net (code "34") (name "Net-(K1-COM)") (class "Default")
      (node (ref "K1") (pin "3") (pinfunction "COM_3") (pintype "bidirectional"))
      (node (ref "K4") (pin "4") (pinfunction "NO_4") (pintype "bidirectional"))
    )
    (net (code "35") (name "Net-(K4-COIL_2)") (class "Default")
      (node (ref "D7") (pin "A") (pinfunction "A_A") (pintype "passive"))
      (node (ref "K4") (pin "2") (pinfunction "COIL_2_2") (pintype "bidirectional"))
      (node (ref "LED7") (pin "C") (pinfunction "C_C") (pintype "passive"))
      (node (ref "Q4") (pin "3") (pinfunction "D_3") (pintype "passive"))
      (node (ref "TP21") (pin "TP") (pinfunction "TP_TP") (pintype "input"))
    )
    (net (code "36") (name "Net-(LED1-PadA)") (class "Default")
      (node (ref "LED1") (pin "A") (pinfunction "A_A") (pintype "passive"))
      (node (ref "R20") (pin "2") (pinfunction "2_2") (pintype "passive"))
    )
    (net (code "37") (name "Net-(LED2-PadA)") (class "Default")
      (node (ref "LED2") (pin "A") (pinfunction "A_A") (pintype "passive"))
      (node (ref "R21") (pin "2") (pinfunction "2_2") (pintype "passive"))
    )
    (net (code "38") (name "Net-(LED3-PadA)") (class "Default")
      (node (ref "LED3") (pin "A") (pinfunction "A_A") (pintype "passive"))
      (node (ref "R22") (pin "2") (pinfunction "2_2") (pintype "passive"))
    )
    (net (code "39") (name "Net-(LED4-PadA)") (class "Default")
      (node (ref "LED4") (pin "A") (pinfunction "A_A") (pintype "passive"))
      (node (ref "R7") (pin "2") (pinfunction "2_2") (pintype "passive"))
    )
    (net (code "40") (name "Net-(LED5-PadA)") (class "Default")
      (node (ref "LED5") (pin "A") (pinfunction "A_A") (pintype "passive"))
      (node (ref "R6") (pin "2") (pinfunction "2_2") (pintype "passive"))
    )
    (net (code "41") (name "Net-(LED6-PadA)") (class "Default")
      (node (ref "LED6") (pin "A") (pinfunction "A_A") (pintype "passive"))
      (node (ref "R8") (pin "2") (pinfunction "2_2") (pintype "passive"))
    )
    (net (code "42") (name "Net-(LED7-PadA)") (class "Default")
      (node (ref "LED7") (pin "A") (pinfunction "A_A") (pintype "passive"))
      (node (ref "R14") (pin "1") (pinfunction "1_1") (pintype "passive"))
    )
    (net (code "43") (name "Net-(LED8-PadA)") (class "Default")
      (node (ref "LED8") (pin "A") (pinfunction "A_A") (pintype "passive"))
      (node (ref "R15") (pin "1") (pinfunction "1_1") (pintype "passive"))
    )
    (net (code "44") (name "Net-(OK2-C)") (class "Default")
      (node (ref "OK2") (pin "3") (pinfunction "C_3") (pintype "passive"))
      (node (ref "R3") (pin "1") (pinfunction "1_1") (pintype "passive"))
    )
    (net (code "45") (name "Net-(POWER/GNDA-S)") (class "Default")
      (node (ref "F1") (pin "2") (pinfunction "2_2") (pintype "bidirectional"))
      (node (ref "POWER/GND") (pin "1") (pinfunction "S_1") (pintype "passive"))
    )
    (net (code "46") (name "Net-(POWER/GNDB-S)") (class "Default")
      (node (ref "F2") (pin "2") (pinfunction "2_2") (pintype "bidirectional"))
      (node (ref "POWER/GND") (pin "2") (pinfunction "S_2") (pintype "passive"))
    )
    (net (code "47") (name "Net-(PRECHARGE/AIRSA-S)") (class "Default")
      (node (ref "K2") (pin "2") (pinfunction "2_2") (pintype "bidirectional"))
      (node (ref "PRECHARGE/AIRS") (pin "1") (pinfunction "S_1") (pintype "passive"))
    )
    (net (code "48") (name "Net-(PRECHARGE/AIRSB-S)") (class "Default")
      (node (ref "K2") (pin "3") (pinfunction "3_3") (pintype "bidirectional"))
      (node (ref "PRECHARGE/AIRS") (pin "2") (pinfunction "S_2") (pintype "passive"))
    )
    (net (code "49") (name "OK_HS") (class "Default")
      (node (ref "ISOMETER_I/O") (pin "8") (pinfunction "8_8") (pintype "bidirectional"))
      (node (ref "OK2") (pin "2") (pinfunction "A_2") (pintype "passive"))
      (node (ref "TP10") (pin "TP") (pinfunction "TP_TP") (pintype "input"))
    )
    (net (code "50") (name "PRECHARGE_SELECT") (class "Default")
      (node (ref "BMS_I/O") (pin "7") (pinfunction "7_7") (pintype "bidirectional"))
      (node (ref "D1") (pin "A") (pinfunction "A_A") (pintype "passive"))
      (node (ref "K2") (pin "5") (pinfunction "5_5") (pintype "bidirectional"))
      (node (ref "LED1") (pin "C") (pinfunction "C_C") (pintype "passive"))
      (node (ref "TP23") (pin "TP") (pinfunction "TP_TP") (pintype "input"))
    )
    (net (code "51") (name "READY_POWER") (class "Default")
      (node (ref "BMS_POWER/GND") (pin "1") (pinfunction "S_1") (pintype "passive"))
      (node (ref "D2") (pin "2") (pinfunction "A_2") (pintype "bidirectional"))
      (node (ref "F2") (pin "1") (pinfunction "1_1") (pintype "bidirectional"))
      (node (ref "THERAL_EX_I/O") (pin "1") (pinfunction "1_1") (pintype "bidirectional"))
      (node (ref "WIFI_I/O") (pin "1") (pinfunction "1_1") (pintype "bidirectional"))
    )
    (net (code "52") (name "STARTUP_RESET") (class "Default")
      (node (ref "IC1") (pin "3") (pinfunction "R0_3") (pintype "input"))
      (node (ref "IC1") (pin "7") (pinfunction "R1_7") (pintype "input"))
      (node (ref "IC2") (pin "3") (pinfunction "Q_3") (pintype "output"))
      (node (ref "R9") (pin "2") (pinfunction "2_2") (pintype "passive"))
      (node (ref "TP4") (pin "TP") (pinfunction "TP_TP") (pintype "input"))
    )
    (net (code "53") (name "unconnected-(CAN1-Pad1)") (class "Default")
      (node (ref "CAN1") (pin "1") (pinfunction "1_1") (pintype "bidirectional"))
    )
    (net (code "54") (name "unconnected-(CAN1-Pad2)") (class "Default")
      (node (ref "CAN1") (pin "2") (pinfunction "2_2") (pintype "bidirectional"))
    )
    (net (code "55") (name "unconnected-(CAN1-Pad4)") (class "Default")
      (node (ref "CAN1") (pin "4") (pinfunction "4_4") (pintype "bidirectional"))
    )
    (net (code "56") (name "unconnected-(CAN1-Pad6)") (class "Default")
      (node (ref "CAN1") (pin "6") (pinfunction "6_6") (pintype "bidirectional"))
    )
    (net (code "57") (name "unconnected-(CAN1-Pad7)") (class "Default")
      (node (ref "CAN1") (pin "7") (pinfunction "7_7") (pintype "bidirectional"))
    )
    (net (code "58") (name "unconnected-(CAN1-Pad8)") (class "Default")
      (node (ref "CAN1") (pin "8") (pinfunction "8_8") (pintype "bidirectional"))
    )
    (net (code "59") (name "unconnected-(CAN1-Pad9)") (class "Default")
      (node (ref "CAN1") (pin "9") (pinfunction "9_9") (pintype "bidirectional"))
    )
    (net (code "60") (name "unconnected-(CAN1-PadMH1)") (class "Default")
      (node (ref "CAN1") (pin "MH1") (pinfunction "MH1_MH1") (pintype "bidirectional"))
    )
    (net (code "61") (name "unconnected-(CAN1-PadMH2)") (class "Default")
      (node (ref "CAN1") (pin "MH2") (pinfunction "MH2_MH2") (pintype "bidirectional"))
    )
    (net (code "62") (name "unconnected-(CAN2-Pad1)") (class "Default")
      (node (ref "CAN2") (pin "1") (pinfunction "1_1") (pintype "bidirectional"))
    )
    (net (code "63") (name "unconnected-(CAN2-Pad2)") (class "Default")
      (node (ref "CAN2") (pin "2") (pinfunction "2_2") (pintype "bidirectional"))
    )
    (net (code "64") (name "unconnected-(CAN2-Pad4)") (class "Default")
      (node (ref "CAN2") (pin "4") (pinfunction "4_4") (pintype "bidirectional"))
    )
    (net (code "65") (name "unconnected-(CAN2-Pad6)") (class "Default")
      (node (ref "CAN2") (pin "6") (pinfunction "6_6") (pintype "bidirectional"))
    )
    (net (code "66") (name "unconnected-(CAN2-Pad7)") (class "Default")
      (node (ref "CAN2") (pin "7") (pinfunction "7_7") (pintype "bidirectional"))
    )
    (net (code "67") (name "unconnected-(CAN2-Pad8)") (class "Default")
      (node (ref "CAN2") (pin "8") (pinfunction "8_8") (pintype "bidirectional"))
    )
    (net (code "68") (name "unconnected-(CAN2-Pad9)") (class "Default")
      (node (ref "CAN2") (pin "9") (pinfunction "9_9") (pintype "bidirectional"))
    )
    (net (code "69") (name "unconnected-(CAN2-PadMH1)") (class "Default")
      (node (ref "CAN2") (pin "MH1") (pinfunction "MH1_MH1") (pintype "bidirectional"))
    )
    (net (code "70") (name "unconnected-(CAN2-PadMH2)") (class "Default")
      (node (ref "CAN2") (pin "MH2") (pinfunction "MH2_MH2") (pintype "bidirectional"))
    )
    (net (code "71") (name "unconnected-(IC1A-Q2-Pad10)") (class "Default")
      (node (ref "IC1") (pin "10") (pinfunction "Q2_10") (pintype "output"))
    )
    (net (code "72") (name "unconnected-(IC1A-Q3-Pad1)") (class "Default")
      (node (ref "IC1") (pin "1") (pinfunction "Q3_1") (pintype "output"))
    )
    (net (code "73") (name "unconnected-(IC4A-~{SHDN}-Pad5)") (class "Default")
      (node (ref "IC4") (pin "5") (pinfunction "~{SHDN}_5") (pintype "input"))
    )
    (net (code "74") (name "unconnected-(ISOMETER_I/O-Pad4)") (class "Default")
      (node (ref "ISOMETER_I/O") (pin "4") (pinfunction "4_4") (pintype "bidirectional"))
    )
    (net (code "75") (name "unconnected-(ISOMETER_I/O-Pad6)") (class "Default")
      (node (ref "ISOMETER_I/O") (pin "6") (pinfunction "6_6") (pintype "bidirectional"))
    )
    (net (code "76") (name "unconnected-(ISOMETER_I/O-Pad7)") (class "Default")
      (node (ref "ISOMETER_I/O") (pin "7") (pinfunction "7_7") (pintype "bidirectional"))
    )
    (net (code "77") (name "unconnected-(THERAL_EX_I/O-Pad7)") (class "Default")
      (node (ref "THERAL_EX_I/O") (pin "7") (pinfunction "7_7") (pintype "bidirectional"))
    )
    (net (code "78") (name "unconnected-(WIFI_I/O-Pad4)") (class "Default")
      (node (ref "WIFI_I/O") (pin "4") (pinfunction "4_4") (pintype "bidirectional"))
    )
    (net (code "79") (name "unconnected-(WIFI_I/O-Pad6)") (class "Default")
      (node (ref "WIFI_I/O") (pin "6") (pinfunction "6_6") (pintype "bidirectional"))
    )
    (net (code "80") (name "unconnected-(WIFI_I/O-Pad7)") (class "Default")
      (node (ref "WIFI_I/O") (pin "7") (pinfunction "7_7") (pintype "bidirectional"))
    )
  )
)
